# new_board.net
KiCad netlist of a schematic drawn in EAGLE
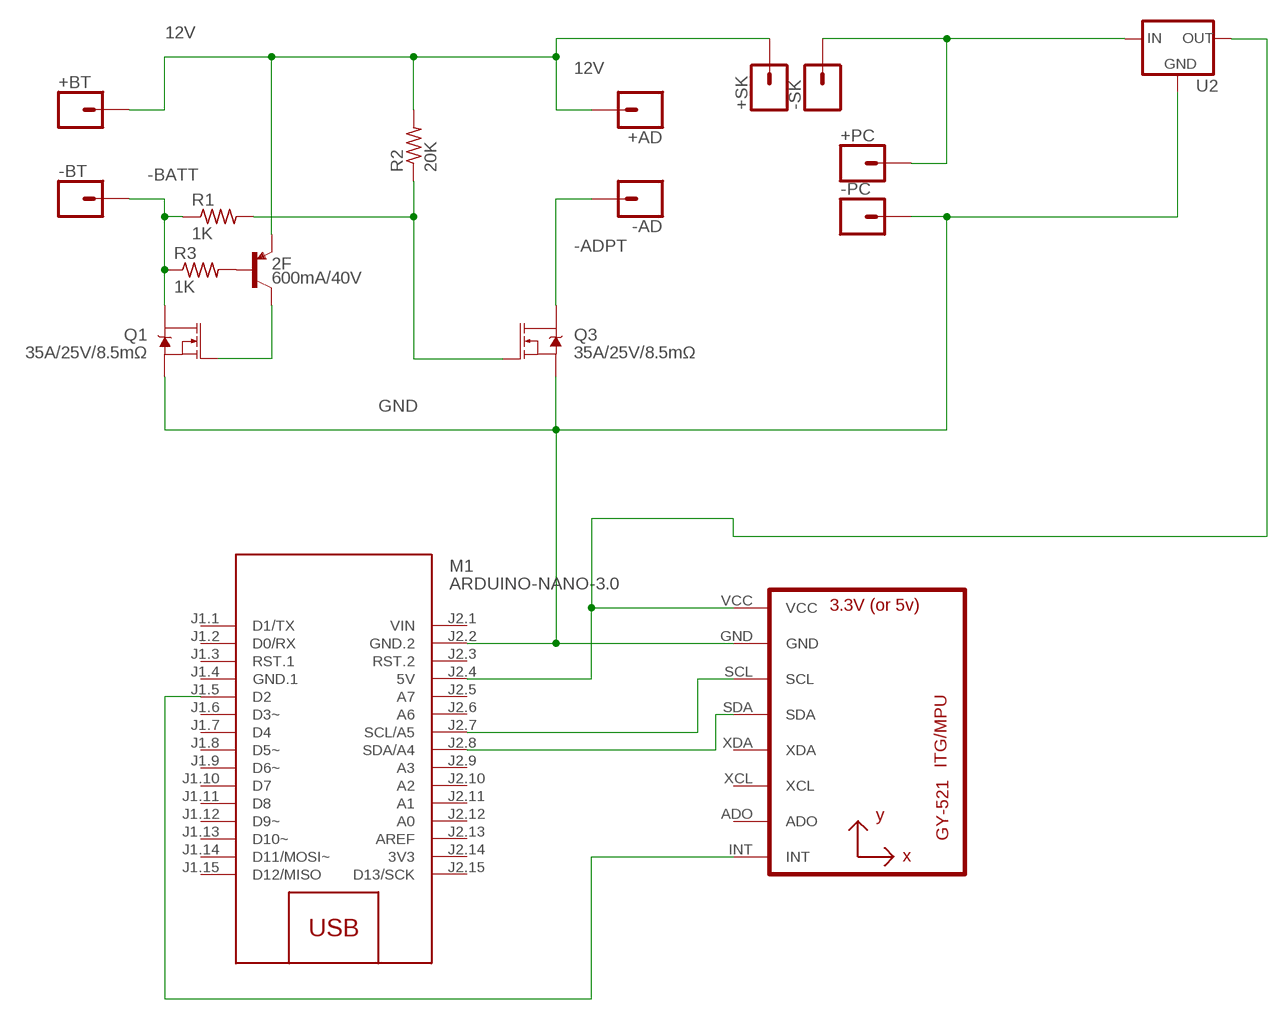
[diagram p0: schematic, sheet 1]

(export (version "E")
  (design (tool "Eeschema 10.0.6"))
  (components
    (comp (ref "+AD")
      (value "CONN_01PTH_2MM")
      (footprint "eagle-import:1X01_2MM")
      (libsource (lib "eagle-import") (part "CONN_01PTH_2MM"))
    )
    (comp (ref "+BT")
      (value "CONN_01PTH_2MM")
      (footprint "eagle-import:1X01_2MM")
      (libsource (lib "eagle-import") (part "CONN_01PTH_2MM"))
    )
    (comp (ref "+PC")
      (value "CONN_01PTH_2MM")
      (footprint "eagle-import:1X01_2MM")
      (libsource (lib "eagle-import") (part "CONN_01PTH_2MM"))
    )
    (comp (ref "+SK")
      (value "CONN_01PTH_2MM")
      (footprint "eagle-import:1X01_2MM")
      (libsource (lib "eagle-import") (part "CONN_01PTH_2MM"))
    )
    (comp (ref "-AD")
      (value "CONN_01PTH_2MM")
      (footprint "eagle-import:1X01_2MM")
      (libsource (lib "eagle-import") (part "CONN_01PTH_2MM"))
    )
    (comp (ref "-BT")
      (value "CONN_01PTH_2MM")
      (footprint "eagle-import:1X01_2MM")
      (libsource (lib "eagle-import") (part "CONN_01PTH_2MM"))
    )
    (comp (ref "-PC")
      (value "CONN_01PTH_2MM")
      (footprint "eagle-import:1X01_2MM")
      (libsource (lib "eagle-import") (part "CONN_01PTH_2MM"))
    )
    (comp (ref "-SK")
      (value "CONN_01PTH_2MM")
      (footprint "eagle-import:1X01_2MM")
      (libsource (lib "eagle-import") (part "CONN_01PTH_2MM"))
    )
    (comp (ref "2F")
      (value "600mA/40V")
      (footprint "eagle-import:SOT23-3")
      (libsource (lib "eagle-import") (part "TRANS_PNP-MMBT4403"))
    )
    (comp (ref "M1")
      (value "ARDUINO-NANO-3.0")
      (footprint "eagle-import:ARDUINO-NANO-3.0")
      (libsource (lib "eagle-import") (part "ARDUINO-NANO-3.0"))
    )
    (comp (ref "Q1")
      (value "35A/25V/8.5mΩ")
      (footprint "eagle-import:DPAK")
      (libsource (lib "eagle-import") (part "MOSFET-NCH-FDD8780"))
    )
    (comp (ref "Q3")
      (value "35A/25V/8.5mΩ")
      (footprint "eagle-import:DPAK")
      (libsource (lib "eagle-import") (part "MOSFET-NCH-FDD8780"))
    )
    (comp (ref "R1")
      (value "1K")
      (footprint "eagle-import:M1206")
      (libsource (lib "eagle-import") (part "R-US_M1206"))
    )
    (comp (ref "R2")
      (value "20K")
      (footprint "eagle-import:M1206")
      (libsource (lib "eagle-import") (part "R-US_M1206"))
    )
    (comp (ref "R3")
      (value "1K")
      (footprint "eagle-import:M1206")
      (libsource (lib "eagle-import") (part "R-US_M1206"))
    )
    (comp (ref "U1")
      (value "GY-521MPU6050")
      (footprint "eagle-import:GY-521")
      (libsource (lib "eagle-import") (part "GY-521MPU6050"))
    )
    (comp (ref "U2")
      (value "+12v")
      (footprint "eagle-import:TO-252")
      (libsource (lib "eagle-import") (part "V_REG_78XX7812"))
    )
  )
  (nets
    (net (code "1") (name "/-ADPT") (class "Default")
      (node (ref "-AD") (pin "1") (pinfunction "1_1") (pintype "passive"))
      (node (ref "Q3") (pin "4") (pinfunction "D_4") (pintype "bidirectional"))
    )
    (net (code "2") (name "/-BATT") (class "Default")
      (node (ref "-BT") (pin "1") (pinfunction "1_1") (pintype "passive"))
      (node (ref "Q1") (pin "4") (pinfunction "D_4") (pintype "bidirectional"))
      (node (ref "R1") (pin "1") (pinfunction "1_1") (pintype "passive"))
      (node (ref "R3") (pin "1") (pinfunction "1_1") (pintype "passive"))
    )
    (net (code "3") (name "/3V3") (class "Default")
      (node (ref "M1") (pin "J2.14") (pinfunction "3V3_J2.14") (pintype "power_in"))
    )
    (net (code "4") (name "/12V") (class "Default")
      (node (ref "+AD") (pin "1") (pinfunction "1_1") (pintype "passive"))
      (node (ref "+BT") (pin "1") (pinfunction "1_1") (pintype "passive"))
      (node (ref "+SK") (pin "1") (pinfunction "1_1") (pintype "passive"))
      (node (ref "2F") (pin "2") (pinfunction "E_2") (pintype "passive"))
      (node (ref "R2") (pin "2") (pinfunction "2_2") (pintype "passive"))
    )
    (net (code "5") (name "/GND") (class "Default")
      (node (ref "-PC") (pin "1") (pinfunction "1_1") (pintype "passive"))
      (node (ref "M1") (pin "J2.2") (pinfunction "GND.2_J2.2") (pintype "power_in"))
      (node (ref "Q1") (pin "3") (pinfunction "S_3") (pintype "bidirectional"))
      (node (ref "Q3") (pin "3") (pinfunction "S_3") (pintype "bidirectional"))
      (node (ref "U1") (pin "GND") (pinfunction "GND_GND") (pintype "bidirectional"))
      (node (ref "U2") (pin "3") (pinfunction "GND_3") (pintype "input"))
    )
    (net (code "6") (name "/GND.1") (class "Default")
      (node (ref "M1") (pin "J1.4") (pinfunction "GND.1_J1.4") (pintype "power_in"))
    )
    (net (code "7") (name "/VIN") (class "Default")
      (node (ref "M1") (pin "J2.1") (pinfunction "VIN_J2.1") (pintype "power_in"))
    )
    (net (code "8") (name "Net-(2F-B)") (class "Default")
      (node (ref "2F") (pin "1") (pinfunction "B_1") (pintype "passive"))
      (node (ref "R3") (pin "2") (pinfunction "2_2") (pintype "passive"))
    )
    (net (code "9") (name "Net-(2F-C)") (class "Default")
      (node (ref "2F") (pin "3") (pinfunction "C_3") (pintype "passive"))
      (node (ref "Q1") (pin "1") (pinfunction "G_1") (pintype "bidirectional"))
    )
    (net (code "10") (name "Net-(M1-5V)") (class "Default")
      (node (ref "M1") (pin "J2.4") (pinfunction "5V_J2.4") (pintype "power_in"))
      (node (ref "U1") (pin "VCC") (pinfunction "VCC_VCC") (pintype "bidirectional"))
      (node (ref "U2") (pin "2") (pinfunction "OUT_2") (pintype "passive"))
    )
    (net (code "11") (name "Net-(M1-D2)") (class "Default")
      (node (ref "M1") (pin "J1.5") (pinfunction "D2_J1.5") (pintype "bidirectional"))
      (node (ref "U1") (pin "INT") (pinfunction "INT_INT") (pintype "bidirectional"))
    )
    (net (code "12") (name "Net-(M1-SCL{slash}A5)") (class "Default")
      (node (ref "M1") (pin "J2.7") (pinfunction "SCL/A5_J2.7") (pintype "bidirectional"))
      (node (ref "U1") (pin "SCL") (pinfunction "SCL_SCL") (pintype "bidirectional"))
    )
    (net (code "13") (name "Net-(M1-SDA{slash}A4)") (class "Default")
      (node (ref "M1") (pin "J2.8") (pinfunction "SDA/A4_J2.8") (pintype "bidirectional"))
      (node (ref "U1") (pin "SDA") (pinfunction "SDA_SDA") (pintype "bidirectional"))
    )
    (net (code "14") (name "Net-(Q3-G)") (class "Default")
      (node (ref "Q3") (pin "1") (pinfunction "G_1") (pintype "bidirectional"))
      (node (ref "R1") (pin "2") (pinfunction "2_2") (pintype "passive"))
      (node (ref "R2") (pin "1") (pinfunction "1_1") (pintype "passive"))
    )
    (net (code "15") (name "Net-(U2-IN)") (class "Default")
      (node (ref "+PC") (pin "1") (pinfunction "1_1") (pintype "passive"))
      (node (ref "-SK") (pin "1") (pinfunction "1_1") (pintype "passive"))
      (node (ref "U2") (pin "1") (pinfunction "IN_1") (pintype "input"))
    )
    (net (code "16") (name "unconnected-(M1-A0-PadJ2.12)") (class "Default")
      (node (ref "M1") (pin "J2.12") (pinfunction "A0_J2.12") (pintype "bidirectional"))
    )
    (net (code "17") (name "unconnected-(M1-A1-PadJ2.11)") (class "Default")
      (node (ref "M1") (pin "J2.11") (pinfunction "A1_J2.11") (pintype "bidirectional"))
    )
    (net (code "18") (name "unconnected-(M1-A2-PadJ2.10)") (class "Default")
      (node (ref "M1") (pin "J2.10") (pinfunction "A2_J2.10") (pintype "bidirectional"))
    )
    (net (code "19") (name "unconnected-(M1-A3-PadJ2.9)") (class "Default")
      (node (ref "M1") (pin "J2.9") (pinfunction "A3_J2.9") (pintype "bidirectional"))
    )
    (net (code "20") (name "unconnected-(M1-A6-PadJ2.6)") (class "Default")
      (node (ref "M1") (pin "J2.6") (pinfunction "A6_J2.6") (pintype "bidirectional"))
    )
    (net (code "21") (name "unconnected-(M1-A7-PadJ2.5)") (class "Default")
      (node (ref "M1") (pin "J2.5") (pinfunction "A7_J2.5") (pintype "bidirectional"))
    )
    (net (code "22") (name "unconnected-(M1-AREF-PadJ2.13)") (class "Default")
      (node (ref "M1") (pin "J2.13") (pinfunction "AREF_J2.13") (pintype "bidirectional"))
    )
    (net (code "23") (name "unconnected-(M1-D0{slash}RX-PadJ1.2)") (class "Default")
      (node (ref "M1") (pin "J1.2") (pinfunction "D0/RX_J1.2") (pintype "bidirectional"))
    )
    (net (code "24") (name "unconnected-(M1-D1{slash}TX-PadJ1.1)") (class "Default")
      (node (ref "M1") (pin "J1.1") (pinfunction "D1/TX_J1.1") (pintype "bidirectional"))
    )
    (net (code "25") (name "unconnected-(M1-D3~{}-PadJ1.6)") (class "Default")
      (node (ref "M1") (pin "J1.6") (pinfunction "D3~{}_J1.6") (pintype "bidirectional"))
    )
    (net (code "26") (name "unconnected-(M1-D4-PadJ1.7)") (class "Default")
      (node (ref "M1") (pin "J1.7") (pinfunction "D4_J1.7") (pintype "bidirectional"))
    )
    (net (code "27") (name "unconnected-(M1-D5~{}-PadJ1.8)") (class "Default")
      (node (ref "M1") (pin "J1.8") (pinfunction "D5~{}_J1.8") (pintype "bidirectional"))
    )
    (net (code "28") (name "unconnected-(M1-D6~{}-PadJ1.9)") (class "Default")
      (node (ref "M1") (pin "J1.9") (pinfunction "D6~{}_J1.9") (pintype "bidirectional"))
    )
    (net (code "29") (name "unconnected-(M1-D7-PadJ1.10)") (class "Default")
      (node (ref "M1") (pin "J1.10") (pinfunction "D7_J1.10") (pintype "bidirectional"))
    )
    (net (code "30") (name "unconnected-(M1-D8-PadJ1.11)") (class "Default")
      (node (ref "M1") (pin "J1.11") (pinfunction "D8_J1.11") (pintype "bidirectional"))
    )
    (net (code "31") (name "unconnected-(M1-D9~{}-PadJ1.12)") (class "Default")
      (node (ref "M1") (pin "J1.12") (pinfunction "D9~{}_J1.12") (pintype "bidirectional"))
    )
    (net (code "32") (name "unconnected-(M1-D10~{}-PadJ1.13)") (class "Default")
      (node (ref "M1") (pin "J1.13") (pinfunction "D10~{}_J1.13") (pintype "bidirectional"))
    )
    (net (code "33") (name "unconnected-(M1-D11{slash}MOSI~{}-PadJ1.14)") (class "Default")
      (node (ref "M1") (pin "J1.14") (pinfunction "D11/MOSI~{}_J1.14") (pintype "bidirectional"))
    )
    (net (code "34") (name "unconnected-(M1-D12{slash}MISO-PadJ1.15)") (class "Default")
      (node (ref "M1") (pin "J1.15") (pinfunction "D12/MISO_J1.15") (pintype "bidirectional"))
    )
    (net (code "35") (name "unconnected-(M1-D13{slash}SCK-PadJ2.15)") (class "Default")
      (node (ref "M1") (pin "J2.15") (pinfunction "D13/SCK_J2.15") (pintype "bidirectional"))
    )
    (net (code "36") (name "unconnected-(M1-RST.1-PadJ1.3)") (class "Default")
      (node (ref "M1") (pin "J1.3") (pinfunction "RST.1_J1.3") (pintype "bidirectional"))
    )
    (net (code "37") (name "unconnected-(M1-RST.2-PadJ2.3)") (class "Default")
      (node (ref "M1") (pin "J2.3") (pinfunction "RST.2_J2.3") (pintype "bidirectional"))
    )
    (net (code "38") (name "unconnected-(U1-PadADO)") (class "Default")
      (node (ref "U1") (pin "ADO") (pinfunction "ADO_ADO") (pintype "bidirectional"))
    )
    (net (code "39") (name "unconnected-(U1-PadXCL)") (class "Default")
      (node (ref "U1") (pin "XCL") (pinfunction "XCL_XCL") (pintype "bidirectional"))
    )
    (net (code "40") (name "unconnected-(U1-PadXDA)") (class "Default")
      (node (ref "U1") (pin "XDA") (pinfunction "XDA_XDA") (pintype "bidirectional"))
    )
  )
)
